# SD_Boot.net
KiCad netlist of a schematic drawn in Altium Designer
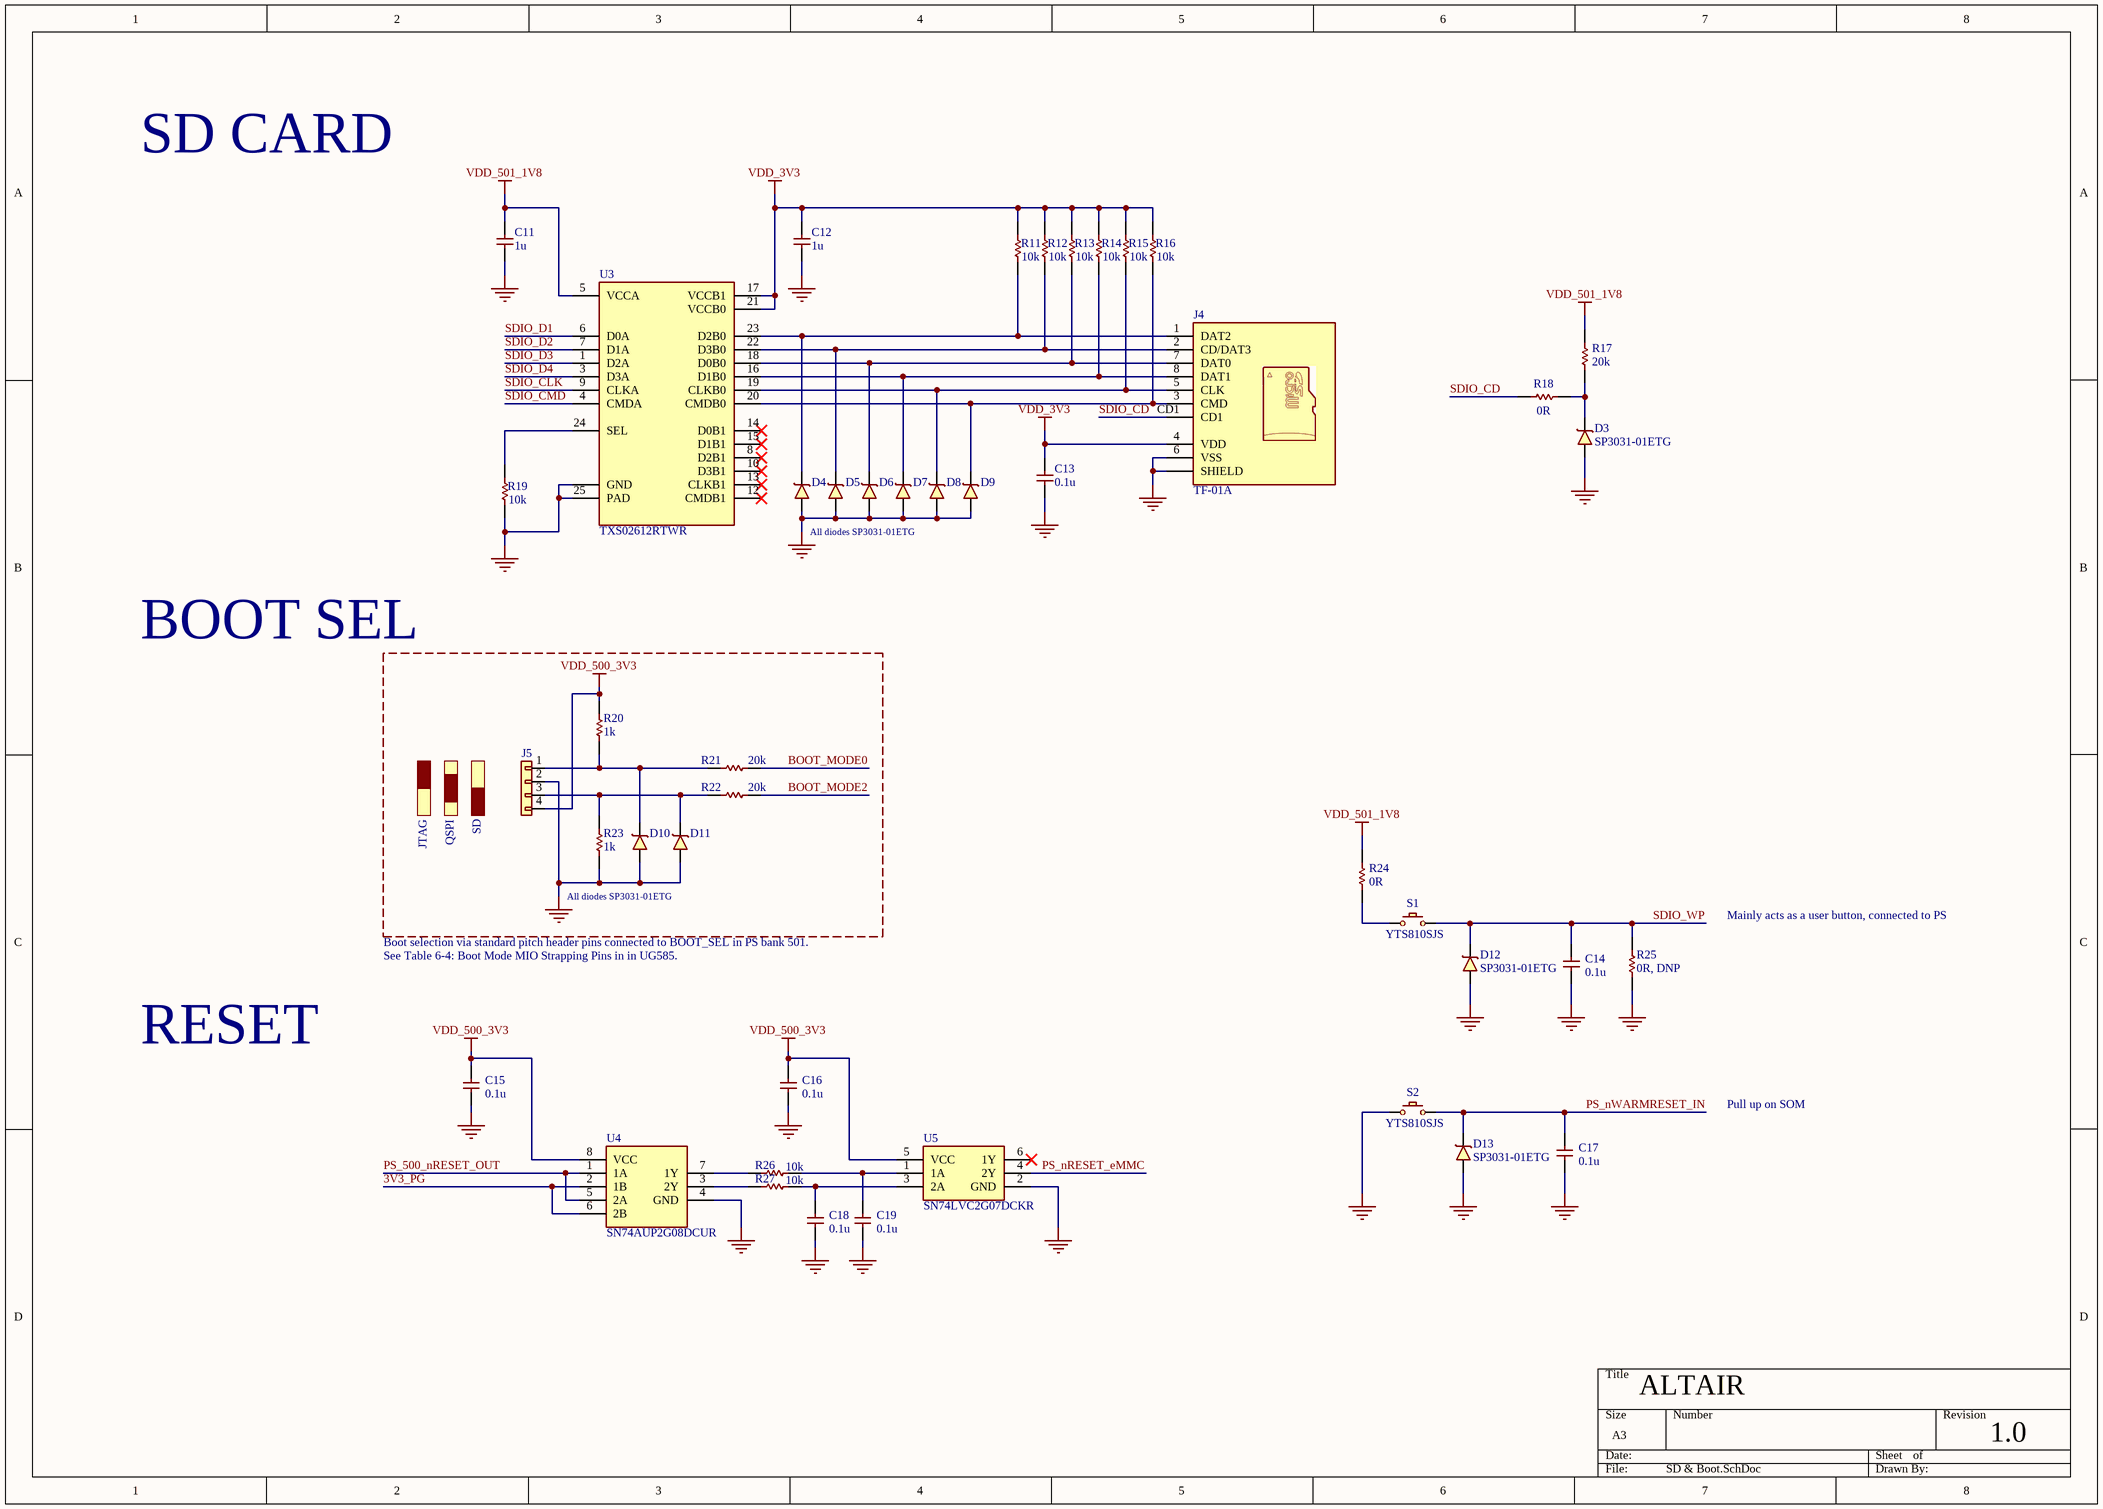
[diagram p0: SD & Boot.SchDoc]

(export (version "E")
  (design (tool "Eeschema 10.0.6"))
  (components
    (comp (ref "C11")
      (value "1u")
      (footprint "CAP_0402")
      (description "Capacitor SMD 0402")
      (fields (field (name "JLCPCB PART #") "C14445") (field (name "PART NO") "CL05A105KP5NNNC"))
      (libsource (lib "personalGenericLib") (part "CAP_0402"))
    )
    (comp (ref "C12")
      (value "1u")
      (footprint "CAP_0402")
      (description "Capacitor SMD 0402")
      (fields (field (name "JLCPCB PART #") "C14445") (field (name "PART NO") "CL05A105KP5NNNC"))
      (libsource (lib "personalGenericLib") (part "CAP_0402"))
    )
    (comp (ref "C13")
      (value "0.1u")
      (footprint "CAP_0402")
      (description "Capacitor SMD 0402")
      (fields (field (name "PART NO") "CL05B104KO5NNNC") (field (name "JLCPCB PART #") "C338112"))
      (libsource (lib "personalGenericLib") (part "CAP_0402"))
    )
    (comp (ref "C14")
      (value "0.1u")
      (footprint "CAP_0402")
      (description "Capacitor SMD 0402")
      (fields (field (name "PART NO") "CL05B104KO5NNNC") (field (name "JLCPCB PART #") "C338112"))
      (libsource (lib "personalGenericLib") (part "CAP_0402"))
    )
    (comp (ref "C15")
      (value "0.1u")
      (footprint "CAP_0402")
      (description "Capacitor SMD 0402")
      (fields (field (name "PART NO") "CL05B104KO5NNNC") (field (name "JLCPCB PART #") "C338112"))
      (libsource (lib "personalGenericLib") (part "CAP_0402"))
    )
    (comp (ref "C16")
      (value "0.1u")
      (footprint "CAP_0402")
      (description "Capacitor SMD 0402")
      (fields (field (name "PART NO") "CL05B104KO5NNNC") (field (name "JLCPCB PART #") "C338112"))
      (libsource (lib "personalGenericLib") (part "CAP_0402"))
    )
    (comp (ref "C17")
      (value "0.1u")
      (footprint "CAP_0402")
      (description "Capacitor SMD 0402")
      (fields (field (name "PART NO") "CL05B104KO5NNNC") (field (name "JLCPCB PART #") "C338112"))
      (libsource (lib "personalGenericLib") (part "CAP_0402"))
    )
    (comp (ref "C18")
      (value "0.1u")
      (footprint "CAP_0402")
      (description "Capacitor SMD 0402")
      (fields (field (name "PART NO") "CL05B104KO5NNNC") (field (name "JLCPCB PART #") "C338112"))
      (libsource (lib "personalGenericLib") (part "CAP_0402"))
    )
    (comp (ref "C19")
      (value "0.1u")
      (footprint "CAP_0402")
      (description "Capacitor SMD 0402")
      (fields (field (name "PART NO") "CL05B104KO5NNNC") (field (name "JLCPCB PART #") "C338112"))
      (libsource (lib "personalGenericLib") (part "CAP_0402"))
    )
    (comp (ref "D3")
      (value "SP3031-01ETG")
      (footprint "SP303101ETG")
      (description "TVS Diode (Uni-directional)")
      (fields (field (name "JLCPCB PART #") "C207283"))
      (libsource (lib "personalGenericLib") (part "SP3031-01ETG"))
    )
    (comp (ref "D4")
      (value "SP3031-01ETG")
      (footprint "SP303101ETG")
      (description "TVS Diode (Uni-directional)")
      (fields (field (name "JLCPCB PART #") "C207283"))
      (libsource (lib "personalGenericLib") (part "SP3031-01ETG"))
    )
    (comp (ref "D5")
      (value "SP3031-01ETG")
      (footprint "SP303101ETG")
      (description "TVS Diode (Uni-directional)")
      (fields (field (name "JLCPCB PART #") "C207283"))
      (libsource (lib "personalGenericLib") (part "SP3031-01ETG"))
    )
    (comp (ref "D6")
      (value "SP3031-01ETG")
      (footprint "SP303101ETG")
      (description "TVS Diode (Uni-directional)")
      (fields (field (name "JLCPCB PART #") "C207283"))
      (libsource (lib "personalGenericLib") (part "SP3031-01ETG"))
    )
    (comp (ref "D7")
      (value "SP3031-01ETG")
      (footprint "SP303101ETG")
      (description "TVS Diode (Uni-directional)")
      (fields (field (name "JLCPCB PART #") "C207283"))
      (libsource (lib "personalGenericLib") (part "SP3031-01ETG"))
    )
    (comp (ref "D8")
      (value "SP3031-01ETG")
      (footprint "SP303101ETG")
      (description "TVS Diode (Uni-directional)")
      (fields (field (name "JLCPCB PART #") "C207283"))
      (libsource (lib "personalGenericLib") (part "SP3031-01ETG"))
    )
    (comp (ref "D9")
      (value "SP3031-01ETG")
      (footprint "SP303101ETG")
      (description "TVS Diode (Uni-directional)")
      (fields (field (name "JLCPCB PART #") "C207283"))
      (libsource (lib "personalGenericLib") (part "SP3031-01ETG"))
    )
    (comp (ref "D10")
      (value "SP3031-01ETG")
      (footprint "SP303101ETG")
      (description "TVS Diode (Uni-directional)")
      (fields (field (name "JLCPCB PART #") "C207283"))
      (libsource (lib "personalGenericLib") (part "SP3031-01ETG"))
    )
    (comp (ref "D11")
      (value "SP3031-01ETG")
      (footprint "SP303101ETG")
      (description "TVS Diode (Uni-directional)")
      (fields (field (name "JLCPCB PART #") "C207283"))
      (libsource (lib "personalGenericLib") (part "SP3031-01ETG"))
    )
    (comp (ref "D12")
      (value "SP3031-01ETG")
      (footprint "SP303101ETG")
      (description "TVS Diode (Uni-directional)")
      (fields (field (name "JLCPCB PART #") "C207283"))
      (libsource (lib "personalGenericLib") (part "SP3031-01ETG"))
    )
    (comp (ref "D13")
      (value "SP3031-01ETG")
      (footprint "SP303101ETG")
      (description "TVS Diode (Uni-directional)")
      (fields (field (name "JLCPCB PART #") "C207283"))
      (libsource (lib "personalGenericLib") (part "SP3031-01ETG"))
    )
    (comp (ref "J4")
      (value "TF-01A")
      (footprint "TF01A")
      (description "SD CARD Connector Slot")
      (fields (field (name "JLCPCB PART #") "C91145"))
      (libsource (lib "personalGenericLib") (part "TF-01A"))
    )
    (comp (ref "J5")
      (value "4xHeader")
      (footprint "HDRV4W95P0X254_1X4_1016X254X854P")
      (description "Standard 4 pin 2.54mm pitch connector")
      (fields (field (name "JLCPCB PART #") "C706876") (field (name "PART NO") "X6511WV-04H-C60D30"))
      (libsource (lib "personalGenericLib") (part "4xHeader"))
    )
    (comp (ref "R11")
      (value "10k")
      (footprint "RES_0402")
      (description "Resistor SMD 0402")
      (fields (field (name "JLCPCB PART #") "C60489") (field (name "PART NO") "RC0402JR-0710KL"))
      (libsource (lib "personalGenericLib") (part "RES_0402"))
    )
    (comp (ref "R12")
      (value "10k")
      (footprint "RES_0402")
      (description "Resistor SMD 0402")
      (fields (field (name "JLCPCB PART #") "C60489") (field (name "PART NO") "RC0402JR-0710KL"))
      (libsource (lib "personalGenericLib") (part "RES_0402"))
    )
    (comp (ref "R13")
      (value "10k")
      (footprint "RES_0402")
      (description "Resistor SMD 0402")
      (fields (field (name "JLCPCB PART #") "C60489") (field (name "PART NO") "RC0402JR-0710KL"))
      (libsource (lib "personalGenericLib") (part "RES_0402"))
    )
    (comp (ref "R14")
      (value "10k")
      (footprint "RES_0402")
      (description "Resistor SMD 0402")
      (fields (field (name "JLCPCB PART #") "C60489") (field (name "PART NO") "RC0402JR-0710KL"))
      (libsource (lib "personalGenericLib") (part "RES_0402"))
    )
    (comp (ref "R15")
      (value "10k")
      (footprint "RES_0402")
      (description "Resistor SMD 0402")
      (fields (field (name "JLCPCB PART #") "C60489") (field (name "PART NO") "RC0402JR-0710KL"))
      (libsource (lib "personalGenericLib") (part "RES_0402"))
    )
    (comp (ref "R16")
      (value "10k")
      (footprint "RES_0402")
      (description "Resistor SMD 0402")
      (fields (field (name "JLCPCB PART #") "C60489") (field (name "PART NO") "RC0402JR-0710KL"))
      (libsource (lib "personalGenericLib") (part "RES_0402"))
    )
    (comp (ref "R17")
      (value "20k")
      (footprint "RES_0402")
      (description "Resistor SMD 0402")
      (fields (field (name "JLCPCB PART #") "C93942") (field (name "PART NO") "RC0402FR-0720KL"))
      (libsource (lib "personalGenericLib") (part "RES_0402"))
    )
    (comp (ref "R18")
      (value "0R")
      (footprint "RES_0402")
      (description "Resistor SMD 0402")
      (fields (field (name "JLCPCB PART #") "C60485") (field (name "PART NO") "RC0402JR-070RL"))
      (libsource (lib "personalGenericLib") (part "RES_0402"))
    )
    (comp (ref "R19")
      (value "10k")
      (footprint "RES_0402")
      (description "Resistor SMD 0402")
      (fields (field (name "JLCPCB PART #") "C60489") (field (name "PART NO") "RC0402JR-0710KL"))
      (libsource (lib "personalGenericLib") (part "RES_0402"))
    )
    (comp (ref "R20")
      (value "1k")
      (footprint "RES_0402")
      (description "Resistor SMD 0402")
      (fields (field (name "JLCPCB PART #") "C105637") (field (name "PART NO") "RC0402JR-071KL"))
      (libsource (lib "personalGenericLib") (part "RES_0402"))
    )
    (comp (ref "R21")
      (value "20k")
      (footprint "RES_0402")
      (description "Resistor SMD 0402")
      (fields (field (name "JLCPCB PART #") "C93942") (field (name "PART NO") "RC0402FR-0720KL"))
      (libsource (lib "personalGenericLib") (part "RES_0402"))
    )
    (comp (ref "R22")
      (value "20k")
      (footprint "RES_0402")
      (description "Resistor SMD 0402")
      (fields (field (name "JLCPCB PART #") "C93942") (field (name "PART NO") "RC0402FR-0720KL"))
      (libsource (lib "personalGenericLib") (part "RES_0402"))
    )
    (comp (ref "R23")
      (value "1k")
      (footprint "RES_0402")
      (description "Resistor SMD 0402")
      (fields (field (name "JLCPCB PART #") "C105637") (field (name "PART NO") "RC0402JR-071KL"))
      (libsource (lib "personalGenericLib") (part "RES_0402"))
    )
    (comp (ref "R24")
      (value "0R")
      (footprint "RES_0402")
      (description "Resistor SMD 0402")
      (fields (field (name "JLCPCB PART #") "C60485") (field (name "PART NO") "RC0402JR-070RL"))
      (libsource (lib "personalGenericLib") (part "RES_0402"))
    )
    (comp (ref "R25")
      (value "0R, DNP")
      (footprint "RES_0402")
      (description "Resistor SMD 0402")
      (fields (field (name "JLCPCB PART #") "C60485") (field (name "PART NO") "RC0402JR-070RL"))
      (libsource (lib "personalGenericLib") (part "RES_0402"))
    )
    (comp (ref "R26")
      (value "10k")
      (footprint "RES_0402")
      (description "Resistor SMD 0402")
      (fields (field (name "JLCPCB PART #") "C60489") (field (name "PART NO") "RC0402JR-0710KL"))
      (libsource (lib "personalGenericLib") (part "RES_0402"))
    )
    (comp (ref "R27")
      (value "10k")
      (footprint "RES_0402")
      (description "Resistor SMD 0402")
      (fields (field (name "JLCPCB PART #") "C60489") (field (name "PART NO") "RC0402JR-0710KL"))
      (libsource (lib "personalGenericLib") (part "RES_0402"))
    )
    (comp (ref "S1")
      (value "YTS810SJS")
      (footprint "YTS810SJS")
      (description "Button SMD 4-Pin")
      (fields (field (name "JLCPCB PART #") "C2910646"))
      (libsource (lib "personalGenericLib") (part "YTS810SJS"))
    )
    (comp (ref "S2")
      (value "YTS810SJS")
      (footprint "YTS810SJS")
      (description "Button SMD 4-Pin")
      (fields (field (name "JLCPCB PART #") "C2910646"))
      (libsource (lib "personalGenericLib") (part "YTS810SJS"))
    )
    (comp (ref "U3")
      (value "TXS02612RTWR")
      (footprint "QFN50P400X400X80-25N-D")
      (description "SD Card Level Shifter Integrated Circuit")
      (fields (field (name "JLCPCB PART #") "C140276"))
      (libsource (lib "personalGenericLib") (part "TXS02612RTWR"))
    )
    (comp (ref "U4")
      (value "SN74AUP2G08DCUR")
      (footprint "SOP50P310X90-8N")
      (description "AND Gate 2 inputs 2 outputs Integrated Circuit")
      (fields (field (name "JLCPCB PART #") "C544478"))
      (libsource (lib "personalGenericLib") (part "SN74AUP2G08DCUR"))
    )
    (comp (ref "U5")
      (value "SN74LVC2G07DCKR")
      (footprint "SOT65P210X110-6N")
      (description "Buffer Gate 1 input 1 output")
      (fields (field (name "JLCPCB PART #") "C7849"))
      (libsource (lib "personalGenericLib") (part "SN74LVC2G07DCKR"))
    )
  )
  (nets
    (net (code "1") (name "/3V3_PG") (class "Default")
      (node (ref "U4") (pin "2") (pinfunction "1B_2") (pintype "passive"))
      (node (ref "U4") (pin "6") (pinfunction "2B_6") (pintype "passive"))
    )
    (net (code "2") (name "/BOOT_MODE0") (class "Default")
      (node (ref "R21") (pin "2") (pinfunction "2_2") (pintype "passive"))
    )
    (net (code "3") (name "/BOOT_MODE2") (class "Default")
      (node (ref "R22") (pin "2") (pinfunction "2_2") (pintype "passive"))
    )
    (net (code "4") (name "/PS_500_nRESET_OUT") (class "Default")
      (node (ref "U4") (pin "1") (pinfunction "1A_1") (pintype "passive"))
      (node (ref "U4") (pin "5") (pinfunction "2A_5") (pintype "passive"))
    )
    (net (code "5") (name "/PS_nRESET_eMMC") (class "Default")
      (node (ref "U5") (pin "4") (pinfunction "2Y_4") (pintype "passive"))
    )
    (net (code "6") (name "/PS_nWARMRESET_IN") (class "Default")
      (node (ref "C17") (pin "2") (pinfunction "2_2") (pintype "passive"))
      (node (ref "D13") (pin "1") (pinfunction "K_1") (pintype "passive"))
      (node (ref "S2") (pin "2") (pinfunction "2_2") (pintype "passive"))
    )
    (net (code "7") (name "/SDIO_CD") (class "Default")
      (node (ref "J4") (pin "CD1") (pinfunction "CD1_CD1") (pintype "passive"))
      (node (ref "R18") (pin "1") (pinfunction "1_1") (pintype "passive"))
    )
    (net (code "8") (name "/SDIO_CLK") (class "Default")
      (node (ref "U3") (pin "9") (pinfunction "CLKA_9") (pintype "passive"))
    )
    (net (code "9") (name "/SDIO_CMD") (class "Default")
      (node (ref "U3") (pin "4") (pinfunction "CMDA_4") (pintype "passive"))
    )
    (net (code "10") (name "/SDIO_D1") (class "Default")
      (node (ref "U3") (pin "6") (pinfunction "D0A_6") (pintype "passive"))
    )
    (net (code "11") (name "/SDIO_D2") (class "Default")
      (node (ref "U3") (pin "7") (pinfunction "D1A_7") (pintype "passive"))
    )
    (net (code "12") (name "/SDIO_D3") (class "Default")
      (node (ref "U3") (pin "1") (pinfunction "D2A_1") (pintype "passive"))
    )
    (net (code "13") (name "/SDIO_D4") (class "Default")
      (node (ref "U3") (pin "3") (pinfunction "D3A_3") (pintype "passive"))
    )
    (net (code "14") (name "/SDIO_WP") (class "Default")
      (node (ref "C14") (pin "2") (pinfunction "2_2") (pintype "passive"))
      (node (ref "D12") (pin "1") (pinfunction "K_1") (pintype "passive"))
      (node (ref "R25") (pin "1") (pinfunction "1_1") (pintype "passive"))
      (node (ref "S1") (pin "2") (pinfunction "2_2") (pintype "passive"))
    )
    (net (code "15") (name "GND") (class "Default")
      (node (ref "C11") (pin "1") (pinfunction "1_1") (pintype "passive"))
      (node (ref "C12") (pin "1") (pinfunction "1_1") (pintype "passive"))
      (node (ref "C13") (pin "1") (pinfunction "1_1") (pintype "passive"))
      (node (ref "C14") (pin "1") (pinfunction "1_1") (pintype "passive"))
      (node (ref "C15") (pin "1") (pinfunction "1_1") (pintype "passive"))
      (node (ref "C16") (pin "1") (pinfunction "1_1") (pintype "passive"))
      (node (ref "C17") (pin "1") (pinfunction "1_1") (pintype "passive"))
      (node (ref "C18") (pin "1") (pinfunction "1_1") (pintype "passive"))
      (node (ref "C19") (pin "1") (pinfunction "1_1") (pintype "passive"))
      (node (ref "D10") (pin "2") (pinfunction "A_2") (pintype "passive"))
      (node (ref "D11") (pin "2") (pinfunction "A_2") (pintype "passive"))
      (node (ref "D12") (pin "2") (pinfunction "A_2") (pintype "passive"))
      (node (ref "D13") (pin "2") (pinfunction "A_2") (pintype "passive"))
      (node (ref "D3") (pin "2") (pinfunction "A_2") (pintype "passive"))
      (node (ref "D4") (pin "2") (pinfunction "A_2") (pintype "passive"))
      (node (ref "D5") (pin "2") (pinfunction "A_2") (pintype "passive"))
      (node (ref "D6") (pin "2") (pinfunction "A_2") (pintype "passive"))
      (node (ref "D7") (pin "2") (pinfunction "A_2") (pintype "passive"))
      (node (ref "D8") (pin "2") (pinfunction "A_2") (pintype "passive"))
      (node (ref "D9") (pin "2") (pinfunction "A_2") (pintype "passive"))
      (node (ref "J4") (pin "6") (pinfunction "VSS_6") (pintype "passive"))
      (node (ref "J4") (pin "SHLD") (pinfunction "SHIELD_SHLD") (pintype "passive"))
      (node (ref "J5") (pin "2") (pinfunction "2_2") (pintype "passive"))
      (node (ref "R19") (pin "2") (pinfunction "2_2") (pintype "passive"))
      (node (ref "R23") (pin "2") (pinfunction "2_2") (pintype "passive"))
      (node (ref "R25") (pin "2") (pinfunction "2_2") (pintype "passive"))
      (node (ref "S2") (pin "1") (pinfunction "1_1") (pintype "passive"))
      (node (ref "U3") (pin "25") (pinfunction "PAD_25") (pintype "passive"))
      (node (ref "U3") (pin "GND") (pinfunction "GND_GND") (pintype "passive"))
      (node (ref "U4") (pin "4") (pinfunction "GND_4") (pintype "passive"))
      (node (ref "U5") (pin "2") (pinfunction "GND_2") (pintype "passive"))
    )
    (net (code "16") (name "Net-(D3-K)") (class "Default")
      (node (ref "D3") (pin "1") (pinfunction "K_1") (pintype "passive"))
      (node (ref "R17") (pin "2") (pinfunction "2_2") (pintype "passive"))
      (node (ref "R18") (pin "2") (pinfunction "2_2") (pintype "passive"))
    )
    (net (code "17") (name "Net-(D4-K)") (class "Default")
      (node (ref "D4") (pin "1") (pinfunction "K_1") (pintype "passive"))
      (node (ref "J4") (pin "1") (pinfunction "DAT2_1") (pintype "passive"))
      (node (ref "R11") (pin "2") (pinfunction "2_2") (pintype "passive"))
      (node (ref "U3") (pin "23") (pinfunction "D2B0_23") (pintype "passive"))
    )
    (net (code "18") (name "Net-(D5-K)") (class "Default")
      (node (ref "D5") (pin "1") (pinfunction "K_1") (pintype "passive"))
      (node (ref "J4") (pin "2") (pinfunction "CD/DAT3_2") (pintype "passive"))
      (node (ref "R12") (pin "2") (pinfunction "2_2") (pintype "passive"))
      (node (ref "U3") (pin "22") (pinfunction "D3B0_22") (pintype "passive"))
    )
    (net (code "19") (name "Net-(D6-K)") (class "Default")
      (node (ref "D6") (pin "1") (pinfunction "K_1") (pintype "passive"))
      (node (ref "J4") (pin "7") (pinfunction "DAT0_7") (pintype "passive"))
      (node (ref "R13") (pin "2") (pinfunction "2_2") (pintype "passive"))
      (node (ref "U3") (pin "18") (pinfunction "D0B0_18") (pintype "passive"))
    )
    (net (code "20") (name "Net-(D7-K)") (class "Default")
      (node (ref "D7") (pin "1") (pinfunction "K_1") (pintype "passive"))
      (node (ref "J4") (pin "8") (pinfunction "DAT1_8") (pintype "passive"))
      (node (ref "R14") (pin "2") (pinfunction "2_2") (pintype "passive"))
      (node (ref "U3") (pin "16") (pinfunction "D1B0_16") (pintype "passive"))
    )
    (net (code "21") (name "Net-(D8-K)") (class "Default")
      (node (ref "D8") (pin "1") (pinfunction "K_1") (pintype "passive"))
      (node (ref "J4") (pin "5") (pinfunction "CLK_5") (pintype "passive"))
      (node (ref "R15") (pin "2") (pinfunction "2_2") (pintype "passive"))
      (node (ref "U3") (pin "19") (pinfunction "CLKB0_19") (pintype "passive"))
    )
    (net (code "22") (name "Net-(D9-K)") (class "Default")
      (node (ref "D9") (pin "1") (pinfunction "K_1") (pintype "passive"))
      (node (ref "J4") (pin "3") (pinfunction "CMD_3") (pintype "passive"))
      (node (ref "R16") (pin "2") (pinfunction "2_2") (pintype "passive"))
      (node (ref "U3") (pin "20") (pinfunction "CMDB0_20") (pintype "passive"))
    )
    (net (code "23") (name "Net-(D10-K)") (class "Default")
      (node (ref "D10") (pin "1") (pinfunction "K_1") (pintype "passive"))
      (node (ref "J5") (pin "1") (pinfunction "1_1") (pintype "passive"))
      (node (ref "R20") (pin "2") (pinfunction "2_2") (pintype "passive"))
      (node (ref "R21") (pin "1") (pinfunction "1_1") (pintype "passive"))
    )
    (net (code "24") (name "Net-(D11-K)") (class "Default")
      (node (ref "D11") (pin "1") (pinfunction "K_1") (pintype "passive"))
      (node (ref "J5") (pin "3") (pinfunction "3_3") (pintype "passive"))
      (node (ref "R22") (pin "1") (pinfunction "1_1") (pintype "passive"))
      (node (ref "R23") (pin "1") (pinfunction "1_1") (pintype "passive"))
    )
    (net (code "25") (name "Net-(R24-Pad2)") (class "Default")
      (node (ref "R24") (pin "2") (pinfunction "2_2") (pintype "passive"))
      (node (ref "S1") (pin "1") (pinfunction "1_1") (pintype "passive"))
    )
    (net (code "26") (name "Net-(U3-SEL)") (class "Default")
      (node (ref "R19") (pin "1") (pinfunction "1_1") (pintype "passive"))
      (node (ref "U3") (pin "24") (pinfunction "SEL_24") (pintype "passive"))
    )
    (net (code "27") (name "Net-(U4-1Y)") (class "Default")
      (node (ref "R26") (pin "1") (pinfunction "1_1") (pintype "passive"))
      (node (ref "U4") (pin "7") (pinfunction "1Y_7") (pintype "passive"))
    )
    (net (code "28") (name "Net-(U4-2Y)") (class "Default")
      (node (ref "R27") (pin "1") (pinfunction "1_1") (pintype "passive"))
      (node (ref "U4") (pin "3") (pinfunction "2Y_3") (pintype "passive"))
    )
    (net (code "29") (name "Net-(U5-1A)") (class "Default")
      (node (ref "C19") (pin "2") (pinfunction "2_2") (pintype "passive"))
      (node (ref "R26") (pin "2") (pinfunction "2_2") (pintype "passive"))
      (node (ref "U5") (pin "1") (pinfunction "1A_1") (pintype "passive"))
    )
    (net (code "30") (name "Net-(U5-2A)") (class "Default")
      (node (ref "C18") (pin "2") (pinfunction "2_2") (pintype "passive"))
      (node (ref "R27") (pin "2") (pinfunction "2_2") (pintype "passive"))
      (node (ref "U5") (pin "3") (pinfunction "2A_3") (pintype "passive"))
    )
    (net (code "31") (name "VDD_3V3") (class "Default")
      (node (ref "C12") (pin "2") (pinfunction "2_2") (pintype "passive"))
      (node (ref "C13") (pin "2") (pinfunction "2_2") (pintype "passive"))
      (node (ref "J4") (pin "4") (pinfunction "VDD_4") (pintype "passive"))
      (node (ref "R11") (pin "1") (pinfunction "1_1") (pintype "passive"))
      (node (ref "R12") (pin "1") (pinfunction "1_1") (pintype "passive"))
      (node (ref "R13") (pin "1") (pinfunction "1_1") (pintype "passive"))
      (node (ref "R14") (pin "1") (pinfunction "1_1") (pintype "passive"))
      (node (ref "R15") (pin "1") (pinfunction "1_1") (pintype "passive"))
      (node (ref "R16") (pin "1") (pinfunction "1_1") (pintype "passive"))
      (node (ref "U3") (pin "17") (pinfunction "VCCB1_17") (pintype "passive"))
      (node (ref "U3") (pin "21") (pinfunction "VCCB0_21") (pintype "passive"))
    )
    (net (code "32") (name "VDD_500_3V3") (class "Default")
      (node (ref "C15") (pin "2") (pinfunction "2_2") (pintype "passive"))
      (node (ref "C16") (pin "2") (pinfunction "2_2") (pintype "passive"))
      (node (ref "J5") (pin "4") (pinfunction "4_4") (pintype "passive"))
      (node (ref "R20") (pin "1") (pinfunction "1_1") (pintype "passive"))
      (node (ref "U4") (pin "8") (pinfunction "VCC_8") (pintype "passive"))
      (node (ref "U5") (pin "5") (pinfunction "VCC_5") (pintype "passive"))
    )
    (net (code "33") (name "VDD_501_1V8") (class "Default")
      (node (ref "C11") (pin "2") (pinfunction "2_2") (pintype "passive"))
      (node (ref "R17") (pin "1") (pinfunction "1_1") (pintype "passive"))
      (node (ref "R24") (pin "1") (pinfunction "1_1") (pintype "passive"))
      (node (ref "U3") (pin "5") (pinfunction "VCCA_5") (pintype "passive"))
    )
    (net (code "34") (name "unconnected-(U3-CLKB1-Pad13)") (class "Default")
      (node (ref "U3") (pin "13") (pinfunction "CLKB1_13") (pintype "passive+no_connect"))
    )
    (net (code "35") (name "unconnected-(U3-CMDB1-Pad12)") (class "Default")
      (node (ref "U3") (pin "12") (pinfunction "CMDB1_12") (pintype "passive+no_connect"))
    )
    (net (code "36") (name "unconnected-(U3-D0B1-Pad14)") (class "Default")
      (node (ref "U3") (pin "14") (pinfunction "D0B1_14") (pintype "passive+no_connect"))
    )
    (net (code "37") (name "unconnected-(U3-D1B1-Pad15)") (class "Default")
      (node (ref "U3") (pin "15") (pinfunction "D1B1_15") (pintype "passive+no_connect"))
    )
    (net (code "38") (name "unconnected-(U3-D2B1-Pad8)") (class "Default")
      (node (ref "U3") (pin "8") (pinfunction "D2B1_8") (pintype "passive+no_connect"))
    )
    (net (code "39") (name "unconnected-(U3-D3B1-Pad10)") (class "Default")
      (node (ref "U3") (pin "10") (pinfunction "D3B1_10") (pintype "passive+no_connect"))
    )
    (net (code "40") (name "unconnected-(U5-1Y-Pad6)") (class "Default")
      (node (ref "U5") (pin "6") (pinfunction "1Y_6") (pintype "passive+no_connect"))
    )
  )
)
